# Pg7-Power_supply_2.net
KiCad netlist of a schematic drawn in Altium Designer
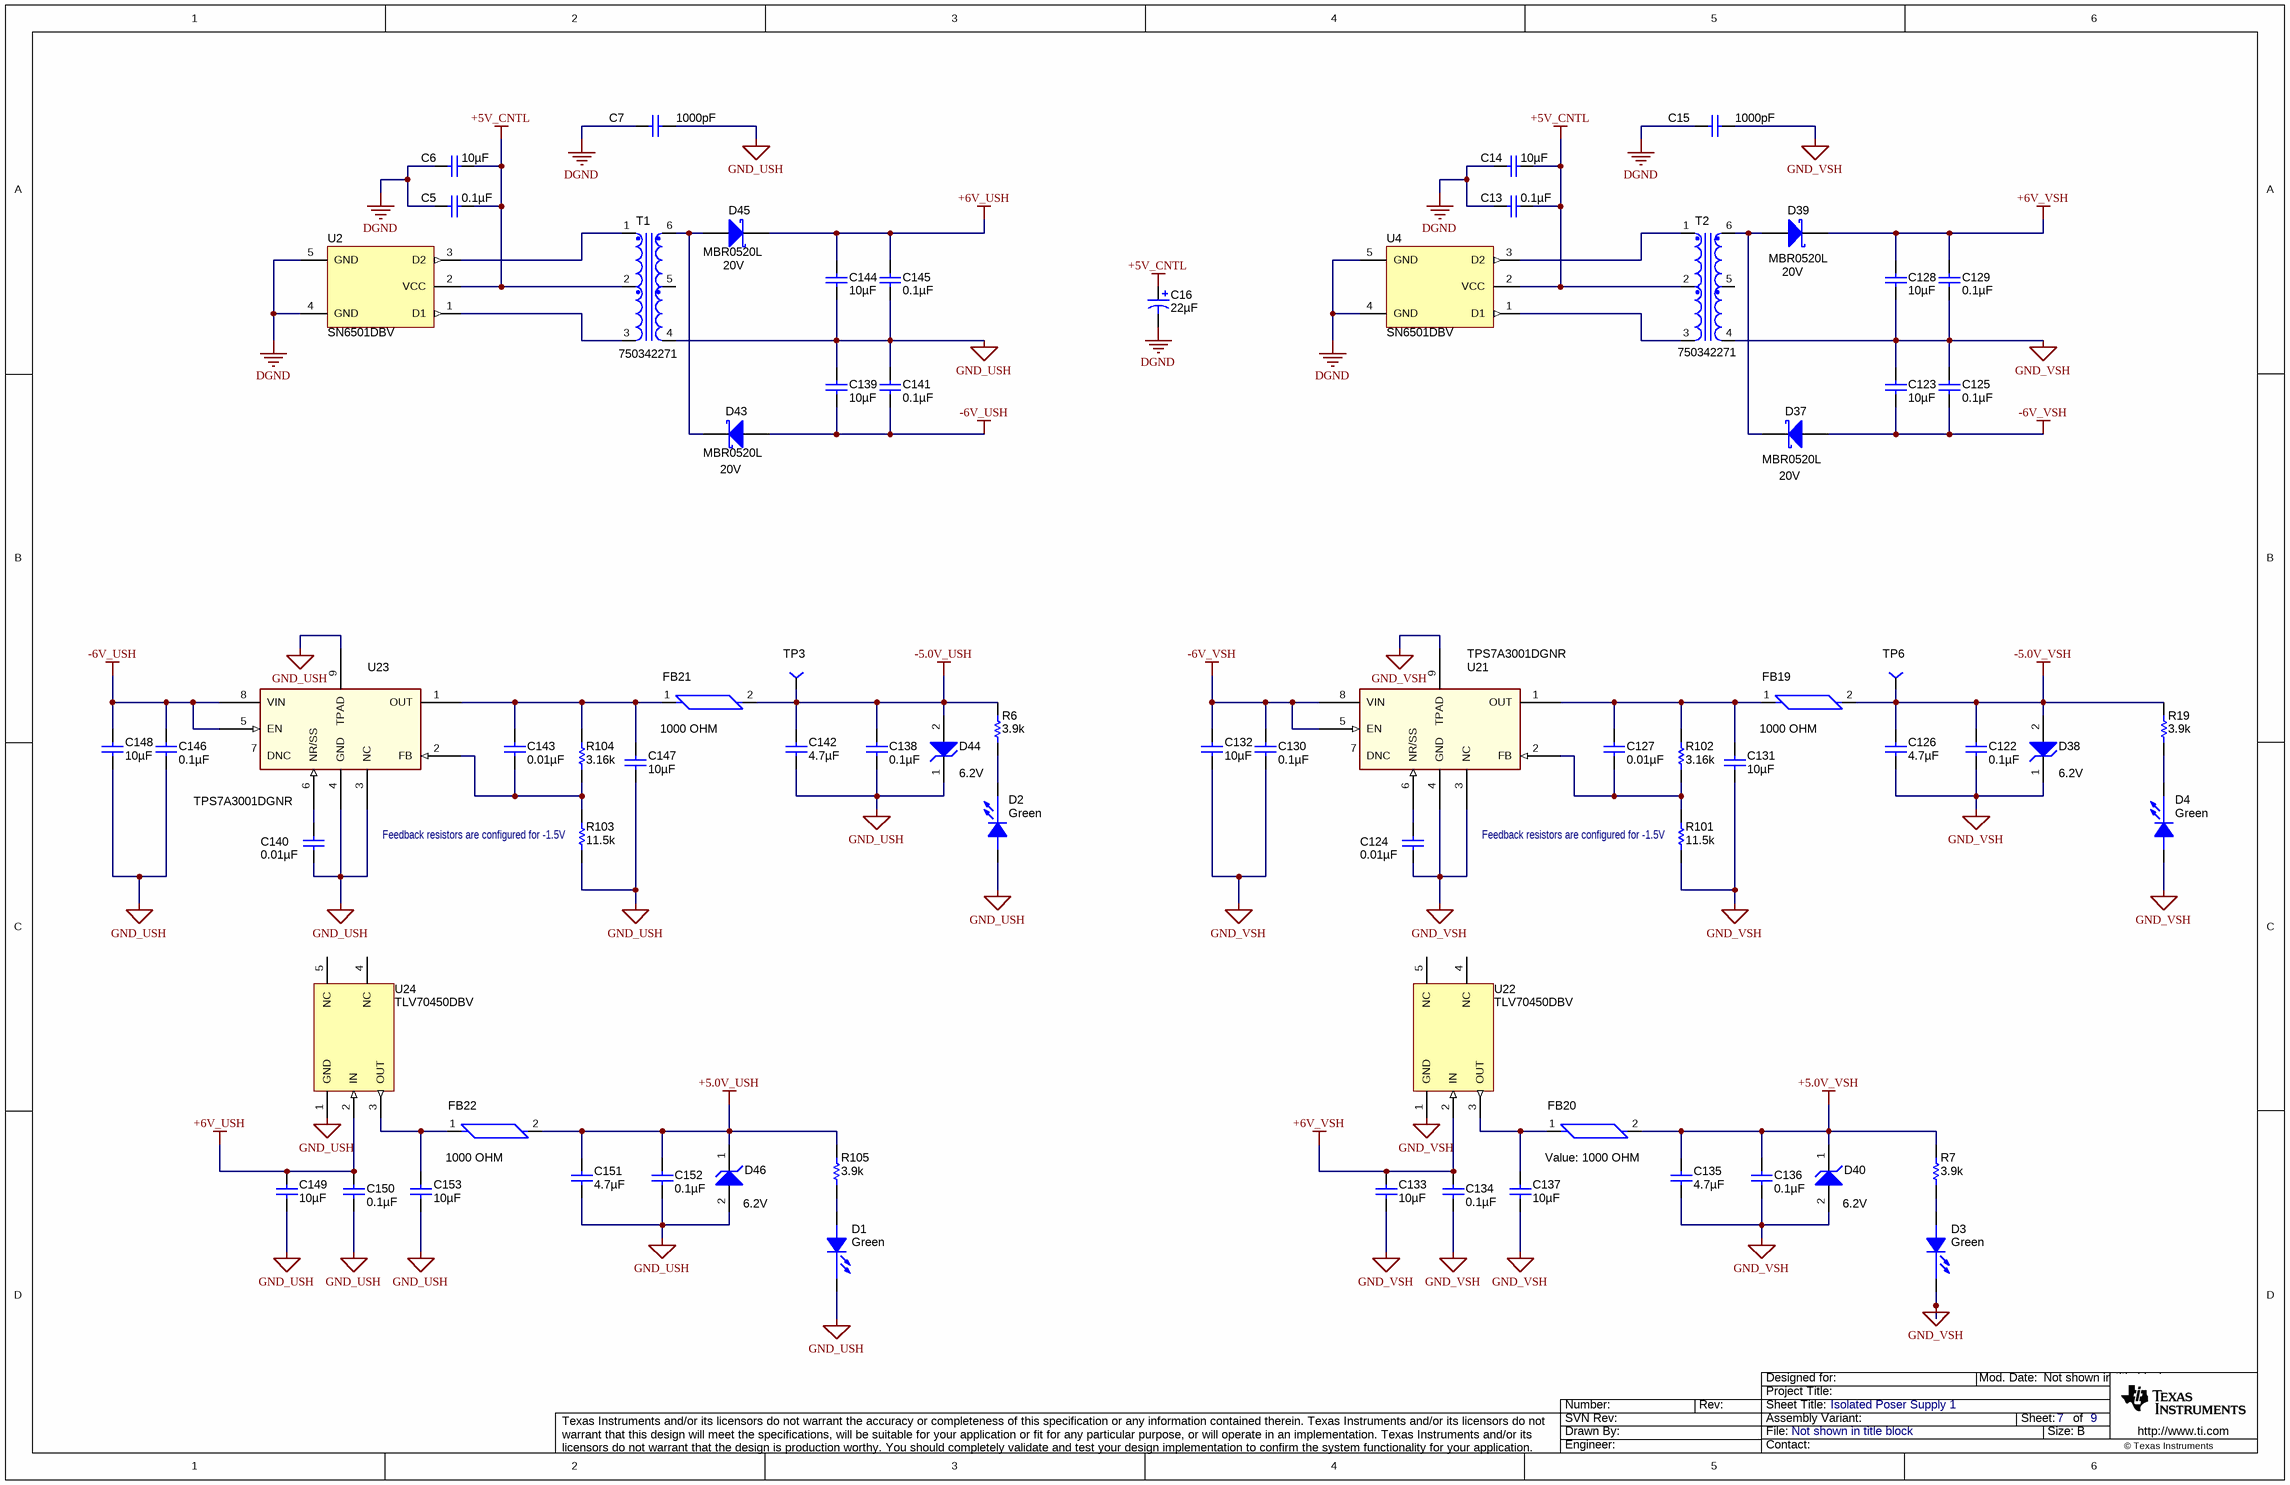
[diagram p0: Pg7-Power supply 2.SchDoc]

(export (version "E")
  (design (tool "Eeschema 10.0.6"))
  (components
    (comp (ref "C5")
      (value "~")
      (footprint "0603")
      (description "CAP, CERM, 0.1uF, 50V, +/-10%, X7R, 0603")
      (fields
        (field (name "PARTNUMBER") "C0603C104K5RACTU")
        (field (name "VALUEDISPLAYED") "0.1µF")
        (field (name "MANUFACTURER") "Kemet")
        (field (name "PUBLISHER") "Texas Instruments")
      )
      (libsource (lib "Capacitor_Ceramic") (part "C0603C104K5RACTU"))
    )
    (comp (ref "C6")
      (value "~")
      (footprint "1210")
      (description "CAP, CERM, 10uF, 35V, +/-20%, X7R, 1210")
      (fields
        (field (name "PARTNUMBER") "GMK325AB7106MM-T")
        (field (name "VALUEDISPLAYED") "10µF")
        (field (name "MANUFACTURER") "Taiyo Yuden")
        (field (name "PUBLISHER") "Texas Instruments")
      )
      (libsource (lib "Capacitor_Ceramic") (part "GMK325AB7106MM-T"))
    )
    (comp (ref "C7")
      (value "1000pF")
      (footprint "CAP_200mil")
      (description "CAP CER 1000PF 1KV 10% RADIAL")
      (fields
        (field (name "PARTNUMBER") "S102K29Y5PN63J5R")
        (field (name "MANUFACTURER") "Vishay BC Components")
        (field (name "PUBLISHER") "Texas Instruments")
      )
      (libsource (lib "TI-INDIA-ALTIUM") (part "202R18W102KV4E"))
    )
    (comp (ref "C13")
      (value "~")
      (footprint "0603")
      (description "CAP, CERM, 0.1uF, 50V, +/-10%, X7R, 0603")
      (fields
        (field (name "PARTNUMBER") "C0603C104K5RACTU")
        (field (name "VALUEDISPLAYED") "0.1µF")
        (field (name "MANUFACTURER") "Kemet")
        (field (name "PUBLISHER") "Texas Instruments")
      )
      (libsource (lib "Capacitor_Ceramic") (part "C0603C104K5RACTU"))
    )
    (comp (ref "C14")
      (value "~")
      (footprint "1210")
      (description "CAP, CERM, 10uF, 35V, +/-20%, X7R, 1210")
      (fields
        (field (name "PARTNUMBER") "GMK325AB7106MM-T")
        (field (name "VALUEDISPLAYED") "10µF")
        (field (name "MANUFACTURER") "Taiyo Yuden")
        (field (name "PUBLISHER") "Texas Instruments")
      )
      (libsource (lib "Capacitor_Ceramic") (part "GMK325AB7106MM-T"))
    )
    (comp (ref "C15")
      (value "1000pF")
      (footprint "CAP_200mil")
      (description "CAP CER 1000PF 1KV 10% RADIAL")
      (fields
        (field (name "PARTNUMBER") "S102K29Y5PN63J5R")
        (field (name "MANUFACTURER") "Vishay BC Components")
        (field (name "PUBLISHER") "Texas Instruments")
      )
      (libsource (lib "TI-INDIA-ALTIUM") (part "202R18W102KV4E"))
    )
    (comp (ref "C16")
      (value "UUD1E220MCL1GS")
      (footprint "SM_RADIAL_5MM")
      (description "CAP, AL, 22uF, 25V, +/-20%, 0.76 ohm, SMD")
      (fields
        (field (name "VALUEDISPLAYED") "22µF")
        (field (name "MANUFACTURER") "Nichicon")
        (field (name "PUBLISHER") "Texas Instruments")
      )
      (libsource (lib "Capacitor_Aluminum") (part "UUD1E220MCL1GS"))
    )
    (comp (ref "C122")
      (value "~")
      (footprint "0603")
      (description "CAP, CERM, 0.1uF, 50V, +/-10%, X7R, 0603")
      (fields
        (field (name "PARTNUMBER") "C0603C104K5RACTU")
        (field (name "VALUEDISPLAYED") "0.1µF")
        (field (name "MANUFACTURER") "Kemet")
        (field (name "PUBLISHER") "Texas Instruments")
      )
      (libsource (lib "Capacitor_Ceramic") (part "C0603C104K5RACTU"))
    )
    (comp (ref "C123")
      (value "~")
      (footprint "1210")
      (description "CAP, CERM, 10uF, 35V, +/-20%, X7R, 1210")
      (fields
        (field (name "PARTNUMBER") "GMK325AB7106MM-T")
        (field (name "VALUEDISPLAYED") "10µF")
        (field (name "MANUFACTURER") "Taiyo Yuden")
        (field (name "PUBLISHER") "Texas Instruments")
      )
      (libsource (lib "Capacitor_Ceramic") (part "GMK325AB7106MM-T"))
    )
    (comp (ref "C124")
      (value "~")
      (footprint "0603")
      (description "CAP, CERM, 0.01uF, 100V, +/-5%, X7R, 0603")
      (fields
        (field (name "PARTNUMBER") "06031C103J4Z4A")
        (field (name "VALUEDISPLAYED") "0.01µF")
        (field (name "MANUFACTURER") "AVX")
        (field (name "PUBLISHER") "Texas Instruments")
      )
      (libsource (lib "Capacitor_Ceramic") (part "06031C103JAT2A"))
    )
    (comp (ref "C125")
      (value "~")
      (footprint "0603")
      (description "CAP, CERM, 0.1uF, 50V, +/-10%, X7R, 0603")
      (fields
        (field (name "PARTNUMBER") "C0603C104K5RACTU")
        (field (name "VALUEDISPLAYED") "0.1µF")
        (field (name "MANUFACTURER") "Kemet")
        (field (name "PUBLISHER") "Texas Instruments")
      )
      (libsource (lib "Capacitor_Ceramic") (part "C0603C104K5RACTU"))
    )
    (comp (ref "C126")
      (value "~")
      (footprint "0805_HV")
      (description "CAP, CERM, 4.7uF, 50V, +/-10%, X5R, 0805")
      (fields
        (field (name "PARTNUMBER") "C2012X5R1H475K125AB")
        (field (name "VALUEDISPLAYED") "4.7µF")
        (field (name "MANUFACTURER") "TDK")
        (field (name "PUBLISHER") "Texas Instruments")
      )
      (libsource (lib "Capacitor_Ceramic") (part "C2012X5R1H475K125AB"))
    )
    (comp (ref "C127")
      (value "~")
      (footprint "0603")
      (description "CAP, CERM, 0.01uF, 100V, +/-5%, X7R, 0603")
      (fields
        (field (name "PARTNUMBER") "06031C103J4Z4A")
        (field (name "VALUEDISPLAYED") "0.01µF")
        (field (name "MANUFACTURER") "AVX")
        (field (name "PUBLISHER") "Texas Instruments")
      )
      (libsource (lib "Capacitor_Ceramic") (part "06031C103JAT2A"))
    )
    (comp (ref "C128")
      (value "~")
      (footprint "1210")
      (description "CAP, CERM, 10uF, 35V, +/-20%, X7R, 1210")
      (fields
        (field (name "PARTNUMBER") "GMK325AB7106MM-T")
        (field (name "VALUEDISPLAYED") "10µF")
        (field (name "MANUFACTURER") "Taiyo Yuden")
        (field (name "PUBLISHER") "Texas Instruments")
      )
      (libsource (lib "Capacitor_Ceramic") (part "GMK325AB7106MM-T"))
    )
    (comp (ref "C129")
      (value "~")
      (footprint "0603")
      (description "CAP, CERM, 0.1uF, 50V, +/-10%, X7R, 0603")
      (fields
        (field (name "PARTNUMBER") "C0603C104K5RACTU")
        (field (name "VALUEDISPLAYED") "0.1µF")
        (field (name "MANUFACTURER") "Kemet")
        (field (name "PUBLISHER") "Texas Instruments")
      )
      (libsource (lib "Capacitor_Ceramic") (part "C0603C104K5RACTU"))
    )
    (comp (ref "C130")
      (value "~")
      (footprint "0603")
      (description "CAP, CERM, 0.1uF, 50V, +/-10%, X7R, 0603")
      (fields
        (field (name "PARTNUMBER") "C0603C104K5RACTU")
        (field (name "VALUEDISPLAYED") "0.1µF")
        (field (name "MANUFACTURER") "Kemet")
        (field (name "PUBLISHER") "Texas Instruments")
      )
      (libsource (lib "Capacitor_Ceramic") (part "C0603C104K5RACTU"))
    )
    (comp (ref "C131")
      (value "~")
      (footprint "1210")
      (description "CAP, CERM, 10uF, 35V, +/-20%, X7R, 1210")
      (fields
        (field (name "PARTNUMBER") "GMK325AB7106MM-T")
        (field (name "VALUEDISPLAYED") "10µF")
        (field (name "MANUFACTURER") "Taiyo Yuden")
        (field (name "PUBLISHER") "Texas Instruments")
      )
      (libsource (lib "Capacitor_Ceramic") (part "GMK325AB7106MM-T"))
    )
    (comp (ref "C132")
      (value "~")
      (footprint "1210")
      (description "CAP, CERM, 10uF, 35V, +/-20%, X7R, 1210")
      (fields
        (field (name "PARTNUMBER") "GMK325AB7106MM-T")
        (field (name "VALUEDISPLAYED") "10µF")
        (field (name "MANUFACTURER") "Taiyo Yuden")
        (field (name "PUBLISHER") "Texas Instruments")
      )
      (libsource (lib "Capacitor_Ceramic") (part "GMK325AB7106MM-T"))
    )
    (comp (ref "C133")
      (value "~")
      (footprint "1210")
      (description "CAP, CERM, 10uF, 35V, +/-20%, X7R, 1210")
      (fields
        (field (name "PARTNUMBER") "GMK325AB7106MM-T")
        (field (name "VALUEDISPLAYED") "10µF")
        (field (name "MANUFACTURER") "Taiyo Yuden")
        (field (name "PUBLISHER") "Texas Instruments")
      )
      (libsource (lib "Capacitor_Ceramic") (part "GMK325AB7106MM-T"))
    )
    (comp (ref "C134")
      (value "~")
      (footprint "0603")
      (description "CAP, CERM, 0.1uF, 50V, +/-10%, X7R, 0603")
      (fields
        (field (name "PARTNUMBER") "C0603C104K5RACTU")
        (field (name "VALUEDISPLAYED") "0.1µF")
        (field (name "MANUFACTURER") "Kemet")
        (field (name "PUBLISHER") "Texas Instruments")
      )
      (libsource (lib "Capacitor_Ceramic") (part "C0603C104K5RACTU"))
    )
    (comp (ref "C135")
      (value "~")
      (footprint "0805_HV")
      (description "CAP, CERM, 4.7uF, 50V, +/-10%, X5R, 0805")
      (fields
        (field (name "PARTNUMBER") "C2012X5R1H475K125AB")
        (field (name "VALUEDISPLAYED") "4.7µF")
        (field (name "MANUFACTURER") "TDK")
        (field (name "PUBLISHER") "Texas Instruments")
      )
      (libsource (lib "Capacitor_Ceramic") (part "C2012X5R1H475K125AB"))
    )
    (comp (ref "C136")
      (value "~")
      (footprint "0603")
      (description "CAP, CERM, 0.1uF, 50V, +/-10%, X7R, 0603")
      (fields
        (field (name "PARTNUMBER") "C0603C104K5RACTU")
        (field (name "VALUEDISPLAYED") "0.1µF")
        (field (name "MANUFACTURER") "Kemet")
        (field (name "PUBLISHER") "Texas Instruments")
      )
      (libsource (lib "Capacitor_Ceramic") (part "C0603C104K5RACTU"))
    )
    (comp (ref "C137")
      (value "~")
      (footprint "1210")
      (description "CAP, CERM, 10uF, 35V, +/-20%, X7R, 1210")
      (fields
        (field (name "PARTNUMBER") "GMK325AB7106MM-T")
        (field (name "VALUEDISPLAYED") "10µF")
        (field (name "MANUFACTURER") "Taiyo Yuden")
        (field (name "PUBLISHER") "Texas Instruments")
      )
      (libsource (lib "Capacitor_Ceramic") (part "GMK325AB7106MM-T"))
    )
    (comp (ref "C138")
      (value "~")
      (footprint "0603")
      (description "CAP, CERM, 0.1uF, 50V, +/-10%, X7R, 0603")
      (fields
        (field (name "PARTNUMBER") "C0603C104K5RACTU")
        (field (name "VALUEDISPLAYED") "0.1µF")
        (field (name "MANUFACTURER") "Kemet")
        (field (name "PUBLISHER") "Texas Instruments")
      )
      (libsource (lib "Capacitor_Ceramic") (part "C0603C104K5RACTU"))
    )
    (comp (ref "C139")
      (value "~")
      (footprint "1210")
      (description "CAP, CERM, 10uF, 35V, +/-20%, X7R, 1210")
      (fields
        (field (name "PARTNUMBER") "GMK325AB7106MM-T")
        (field (name "VALUEDISPLAYED") "10µF")
        (field (name "MANUFACTURER") "Taiyo Yuden")
        (field (name "PUBLISHER") "Texas Instruments")
      )
      (libsource (lib "Capacitor_Ceramic") (part "GMK325AB7106MM-T"))
    )
    (comp (ref "C140")
      (value "~")
      (footprint "0603")
      (description "CAP, CERM, 0.01uF, 100V, +/-5%, X7R, 0603")
      (fields
        (field (name "PARTNUMBER") "06031C103J4Z4A")
        (field (name "VALUEDISPLAYED") "0.01µF")
        (field (name "MANUFACTURER") "AVX")
        (field (name "PUBLISHER") "Texas Instruments")
      )
      (libsource (lib "Capacitor_Ceramic") (part "06031C103JAT2A"))
    )
    (comp (ref "C141")
      (value "~")
      (footprint "0603")
      (description "CAP, CERM, 0.1uF, 50V, +/-10%, X7R, 0603")
      (fields
        (field (name "PARTNUMBER") "C0603C104K5RACTU")
        (field (name "VALUEDISPLAYED") "0.1µF")
        (field (name "MANUFACTURER") "Kemet")
        (field (name "PUBLISHER") "Texas Instruments")
      )
      (libsource (lib "Capacitor_Ceramic") (part "C0603C104K5RACTU"))
    )
    (comp (ref "C142")
      (value "~")
      (footprint "0805_HV")
      (description "CAP, CERM, 4.7uF, 50V, +/-10%, X5R, 0805")
      (fields
        (field (name "PARTNUMBER") "C2012X5R1H475K125AB")
        (field (name "VALUEDISPLAYED") "4.7µF")
        (field (name "MANUFACTURER") "TDK")
        (field (name "PUBLISHER") "Texas Instruments")
      )
      (libsource (lib "Capacitor_Ceramic") (part "C2012X5R1H475K125AB"))
    )
    (comp (ref "C143")
      (value "~")
      (footprint "0603")
      (description "CAP, CERM, 0.01uF, 100V, +/-5%, X7R, 0603")
      (fields
        (field (name "PARTNUMBER") "06031C103J4Z4A")
        (field (name "VALUEDISPLAYED") "0.01µF")
        (field (name "MANUFACTURER") "AVX")
        (field (name "PUBLISHER") "Texas Instruments")
      )
      (libsource (lib "Capacitor_Ceramic") (part "06031C103JAT2A"))
    )
    (comp (ref "C144")
      (value "~")
      (footprint "1210")
      (description "CAP, CERM, 10uF, 35V, +/-20%, X7R, 1210")
      (fields
        (field (name "PARTNUMBER") "GMK325AB7106MM-T")
        (field (name "VALUEDISPLAYED") "10µF")
        (field (name "MANUFACTURER") "Taiyo Yuden")
        (field (name "PUBLISHER") "Texas Instruments")
      )
      (libsource (lib "Capacitor_Ceramic") (part "GMK325AB7106MM-T"))
    )
    (comp (ref "C145")
      (value "~")
      (footprint "0603")
      (description "CAP, CERM, 0.1uF, 50V, +/-10%, X7R, 0603")
      (fields
        (field (name "PARTNUMBER") "C0603C104K5RACTU")
        (field (name "VALUEDISPLAYED") "0.1µF")
        (field (name "MANUFACTURER") "Kemet")
        (field (name "PUBLISHER") "Texas Instruments")
      )
      (libsource (lib "Capacitor_Ceramic") (part "C0603C104K5RACTU"))
    )
    (comp (ref "C146")
      (value "~")
      (footprint "0603")
      (description "CAP, CERM, 0.1uF, 50V, +/-10%, X7R, 0603")
      (fields
        (field (name "PARTNUMBER") "C0603C104K5RACTU")
        (field (name "VALUEDISPLAYED") "0.1µF")
        (field (name "MANUFACTURER") "Kemet")
        (field (name "PUBLISHER") "Texas Instruments")
      )
      (libsource (lib "Capacitor_Ceramic") (part "C0603C104K5RACTU"))
    )
    (comp (ref "C147")
      (value "~")
      (footprint "1210")
      (description "CAP, CERM, 10uF, 35V, +/-20%, X7R, 1210")
      (fields
        (field (name "PARTNUMBER") "GMK325AB7106MM-T")
        (field (name "VALUEDISPLAYED") "10µF")
        (field (name "MANUFACTURER") "Taiyo Yuden")
        (field (name "PUBLISHER") "Texas Instruments")
      )
      (libsource (lib "Capacitor_Ceramic") (part "GMK325AB7106MM-T"))
    )
    (comp (ref "C148")
      (value "~")
      (footprint "1210")
      (description "CAP, CERM, 10uF, 35V, +/-20%, X7R, 1210")
      (fields
        (field (name "PARTNUMBER") "GMK325AB7106MM-T")
        (field (name "VALUEDISPLAYED") "10µF")
        (field (name "MANUFACTURER") "Taiyo Yuden")
        (field (name "PUBLISHER") "Texas Instruments")
      )
      (libsource (lib "Capacitor_Ceramic") (part "GMK325AB7106MM-T"))
    )
    (comp (ref "C149")
      (value "~")
      (footprint "1210")
      (description "CAP, CERM, 10uF, 35V, +/-20%, X7R, 1210")
      (fields
        (field (name "PARTNUMBER") "GMK325AB7106MM-T")
        (field (name "VALUEDISPLAYED") "10µF")
        (field (name "MANUFACTURER") "Taiyo Yuden")
        (field (name "PUBLISHER") "Texas Instruments")
      )
      (libsource (lib "Capacitor_Ceramic") (part "GMK325AB7106MM-T"))
    )
    (comp (ref "C150")
      (value "~")
      (footprint "0603")
      (description "CAP, CERM, 0.1uF, 50V, +/-10%, X7R, 0603")
      (fields
        (field (name "PARTNUMBER") "C0603C104K5RACTU")
        (field (name "VALUEDISPLAYED") "0.1µF")
        (field (name "MANUFACTURER") "Kemet")
        (field (name "PUBLISHER") "Texas Instruments")
      )
      (libsource (lib "Capacitor_Ceramic") (part "C0603C104K5RACTU"))
    )
    (comp (ref "C151")
      (value "~")
      (footprint "0805_HV")
      (description "CAP, CERM, 4.7uF, 50V, +/-10%, X5R, 0805")
      (fields
        (field (name "PARTNUMBER") "C2012X5R1H475K125AB")
        (field (name "VALUEDISPLAYED") "4.7µF")
        (field (name "MANUFACTURER") "TDK")
        (field (name "PUBLISHER") "Texas Instruments")
      )
      (libsource (lib "Capacitor_Ceramic") (part "C2012X5R1H475K125AB"))
    )
    (comp (ref "C152")
      (value "~")
      (footprint "0603")
      (description "CAP, CERM, 0.1uF, 50V, +/-10%, X7R, 0603")
      (fields
        (field (name "PARTNUMBER") "C0603C104K5RACTU")
        (field (name "VALUEDISPLAYED") "0.1µF")
        (field (name "MANUFACTURER") "Kemet")
        (field (name "PUBLISHER") "Texas Instruments")
      )
      (libsource (lib "Capacitor_Ceramic") (part "C0603C104K5RACTU"))
    )
    (comp (ref "C153")
      (value "~")
      (footprint "1210")
      (description "CAP, CERM, 10uF, 35V, +/-20%, X7R, 1210")
      (fields
        (field (name "PARTNUMBER") "GMK325AB7106MM-T")
        (field (name "VALUEDISPLAYED") "10µF")
        (field (name "MANUFACTURER") "Taiyo Yuden")
        (field (name "PUBLISHER") "Texas Instruments")
      )
      (libsource (lib "Capacitor_Ceramic") (part "GMK325AB7106MM-T"))
    )
    (comp (ref "D1")
      (value "Green")
      (footprint "LED0603AA")
      (description "LED SmartLED Green 570NM")
      (fields
        (field (name "PARTNUMBER") "LG L29K-G2J1-24-Z")
        (field (name "MANUFACTURER") "OSRAM")
        (field (name "PUBLISHER") "TI")
        (field (name "SYMBOLCREATOR") "x0120606")
      )
      (libsource (lib "TI-INDIA-ALTIUM") (part "LED_LG L29K-G2J1-24-Z"))
    )
    (comp (ref "D2")
      (value "Green")
      (footprint "LED0603AA")
      (description "LED SmartLED Green 570NM")
      (fields
        (field (name "PARTNUMBER") "LG L29K-G2J1-24-Z")
        (field (name "MANUFACTURER") "OSRAM")
        (field (name "PUBLISHER") "TI")
        (field (name "SYMBOLCREATOR") "x0120606")
      )
      (libsource (lib "TI-INDIA-ALTIUM") (part "LED_LG L29K-G2J1-24-Z"))
    )
    (comp (ref "D3")
      (value "Green")
      (footprint "LED0603AA")
      (description "LED SmartLED Green 570NM")
      (fields
        (field (name "PARTNUMBER") "LG L29K-G2J1-24-Z")
        (field (name "MANUFACTURER") "OSRAM")
        (field (name "PUBLISHER") "TI")
        (field (name "SYMBOLCREATOR") "x0120606")
      )
      (libsource (lib "TI-INDIA-ALTIUM") (part "LED_LG L29K-G2J1-24-Z"))
    )
    (comp (ref "D4")
      (value "Green")
      (footprint "LED0603AA")
      (description "LED SmartLED Green 570NM")
      (fields
        (field (name "PARTNUMBER") "LG L29K-G2J1-24-Z")
        (field (name "MANUFACTURER") "OSRAM")
        (field (name "PUBLISHER") "TI")
        (field (name "SYMBOLCREATOR") "x0120606")
      )
      (libsource (lib "TI-INDIA-ALTIUM") (part "LED_LG L29K-G2J1-24-Z"))
    )
    (comp (ref "D37")
      (value "MBR0520L")
      (footprint "SOD-123")
      (description "Diode, Schottky, 20V, 0.5A, SOD-123")
      (fields
        (field (name "ALTIUM_VALUE") "20V")
        (field (name "MANUFACTURER") "Fairchild Semiconductor")
        (field (name "PUBLISHER") "Texas Instruments")
      )
      (libsource (lib "Diode") (part "MBR0520LT1G"))
    )
    (comp (ref "D38")
      (value "6.2V")
      (footprint "powerDI123")
      (description "Diode, Zener, 6.2V, 1W, PowerDI123")
      (fields
        (field (name "PARTNUMBER") "DFLZ6V2-7")
        (field (name "MANUFACTURER") "Diodes Inc.")
        (field (name "PUBLISHER") "Texas Instruments")
      )
      (libsource (lib "ZenerDiodes") (part "DFLZ6V2-7"))
    )
    (comp (ref "D39")
      (value "MBR0520L")
      (footprint "SOD-123")
      (description "Diode, Schottky, 20V, 0.5A, SOD-123")
      (fields
        (field (name "ALTIUM_VALUE") "20V")
        (field (name "MANUFACTURER") "Fairchild Semiconductor")
        (field (name "PUBLISHER") "Texas Instruments")
      )
      (libsource (lib "Diode") (part "MBR0520LT1G"))
    )
    (comp (ref "D40")
      (value "6.2V")
      (footprint "powerDI123")
      (description "Diode, Zener, 6.2V, 1W, PowerDI123")
      (fields
        (field (name "PARTNUMBER") "DFLZ6V2-7")
        (field (name "MANUFACTURER") "Diodes Inc.")
        (field (name "PUBLISHER") "Texas Instruments")
      )
      (libsource (lib "ZenerDiodes") (part "DFLZ6V2-7"))
    )
    (comp (ref "D43")
      (value "MBR0520L")
      (footprint "SOD-123")
      (description "Diode, Schottky, 20V, 0.5A, SOD-123")
      (fields
        (field (name "ALTIUM_VALUE") "20V")
        (field (name "MANUFACTURER") "Fairchild Semiconductor")
        (field (name "PUBLISHER") "Texas Instruments")
      )
      (libsource (lib "Diode") (part "MBR0520LT1G"))
    )
    (comp (ref "D44")
      (value "6.2V")
      (footprint "powerDI123")
      (description "Diode, Zener, 6.2V, 1W, PowerDI123")
      (fields
        (field (name "PARTNUMBER") "DFLZ6V2-7")
        (field (name "MANUFACTURER") "Diodes Inc.")
        (field (name "PUBLISHER") "Texas Instruments")
      )
      (libsource (lib "ZenerDiodes") (part "DFLZ6V2-7"))
    )
    (comp (ref "D45")
      (value "MBR0520L")
      (footprint "SOD-123")
      (description "Diode, Schottky, 20V, 0.5A, SOD-123")
      (fields
        (field (name "ALTIUM_VALUE") "20V")
        (field (name "MANUFACTURER") "Fairchild Semiconductor")
        (field (name "PUBLISHER") "Texas Instruments")
      )
      (libsource (lib "Diode") (part "MBR0520LT1G"))
    )
    (comp (ref "D46")
      (value "6.2V")
      (footprint "powerDI123")
      (description "Diode, Zener, 6.2V, 1W, PowerDI123")
      (fields
        (field (name "PARTNUMBER") "DFLZ6V2-7")
        (field (name "MANUFACTURER") "Diodes Inc.")
        (field (name "PUBLISHER") "Texas Instruments")
      )
      (libsource (lib "ZenerDiodes") (part "DFLZ6V2-7"))
    )
    (comp (ref "FB19")
      (value "1000 OHM")
      (footprint "FB0603")
      (description "FERRITE CHIP 1000 OHM 300MA 0603")
      (fields
        (field (name "PARTNUMBER") "MMZ1608B102C")
        (field (name "MANUFACTURER") "TDK Corporation")
        (field (name "PUBLISHER") "TI")
      )
      (libsource (lib "TI-INDIA-ALTIUM") (part "MMZ1608B102C"))
    )
    (comp (ref "FB20")
      (value "1000 OHM")
      (footprint "FB0603")
      (description "FERRITE CHIP 1000 OHM 300MA 0603")
      (fields
        (field (name "PARTNUMBER") "MMZ1608B102C")
        (field (name "MANUFACTURER") "TDK Corporation")
        (field (name "PUBLISHER") "TI")
      )
      (libsource (lib "TI-INDIA-ALTIUM") (part "MMZ1608B102C"))
    )
    (comp (ref "FB21")
      (value "1000 OHM")
      (footprint "FB0603")
      (description "FERRITE CHIP 1000 OHM 300MA 0603")
      (fields
        (field (name "PARTNUMBER") "MMZ1608B102C")
        (field (name "MANUFACTURER") "TDK Corporation")
        (field (name "PUBLISHER") "TI")
      )
      (libsource (lib "TI-INDIA-ALTIUM") (part "MMZ1608B102C"))
    )
    (comp (ref "FB22")
      (value "1000 OHM")
      (footprint "FB0603")
      (description "FERRITE CHIP 1000 OHM 300MA 0603")
      (fields
        (field (name "PARTNUMBER") "MMZ1608B102C")
        (field (name "MANUFACTURER") "TDK Corporation")
        (field (name "PUBLISHER") "TI")
      )
      (libsource (lib "TI-INDIA-ALTIUM") (part "MMZ1608B102C"))
    )
    (comp (ref "R6")
      (value "3.9k")
      (footprint "0603")
      (description "RES, 3.9k ohm, 5%, 0.1W, 0603")
      (fields
        (field (name "PARTNUMBER") "CRCW06033K90JNEA")
        (field (name "MANUFACTURER") "Vishay-Dale")
        (field (name "PUBLISHER") "Texas Instruments")
      )
      (libsource (lib "Resistor_0603") (part "CRCW06033K90JNEA"))
    )
    (comp (ref "R7")
      (value "3.9k")
      (footprint "0603")
      (description "RES, 3.9k ohm, 5%, 0.1W, 0603")
      (fields
        (field (name "PARTNUMBER") "CRCW06033K90JNEA")
        (field (name "MANUFACTURER") "Vishay-Dale")
        (field (name "PUBLISHER") "Texas Instruments")
      )
      (libsource (lib "Resistor_0603") (part "CRCW06033K90JNEA"))
    )
    (comp (ref "R19")
      (value "3.9k")
      (footprint "0603")
      (description "RES, 3.9k ohm, 5%, 0.1W, 0603")
      (fields
        (field (name "PARTNUMBER") "CRCW06033K90JNEA")
        (field (name "MANUFACTURER") "Vishay-Dale")
        (field (name "PUBLISHER") "Texas Instruments")
      )
      (libsource (lib "Resistor_0603") (part "CRCW06033K90JNEA"))
    )
    (comp (ref "R101")
      (value "11.5k")
      (footprint "0603")
      (description "RES, 11.5k ohm, 1%, 0.1W, 0603")
      (fields
        (field (name "PARTNUMBER") "CRCW060311K5FKEA")
        (field (name "MANUFACTURER") "Vishay-Dale")
        (field (name "PUBLISHER") "Texas Instruments")
      )
      (libsource (lib "Resistor_0603") (part "CRCW060311K5FKEA"))
    )
    (comp (ref "R102")
      (value "RC0603FR-073K16L")
      (footprint "0603")
      (description "RES, 3.16 k, 1%, 0.1 W, 0603")
      (fields
        (field (name "VALUEDISPLAYED") "3.16k")
        (field (name "MANUFACTURER") "Yageo America")
        (field (name "PUBLISHER") "Texas Instruments")
      )
      (libsource (lib "Resistor_0603") (part "RC0603FR-073K16L"))
    )
    (comp (ref "R103")
      (value "11.5k")
      (footprint "0603")
      (description "RES, 11.5k ohm, 1%, 0.1W, 0603")
      (fields
        (field (name "PARTNUMBER") "CRCW060311K5FKEA")
        (field (name "MANUFACTURER") "Vishay-Dale")
        (field (name "PUBLISHER") "Texas Instruments")
      )
      (libsource (lib "Resistor_0603") (part "CRCW060311K5FKEA"))
    )
    (comp (ref "R104")
      (value "RC0603FR-073K16L")
      (footprint "0603")
      (description "RES, 3.16 k, 1%, 0.1 W, 0603")
      (fields
        (field (name "VALUEDISPLAYED") "3.16k")
        (field (name "MANUFACTURER") "Yageo America")
        (field (name "PUBLISHER") "Texas Instruments")
      )
      (libsource (lib "Resistor_0603") (part "RC0603FR-073K16L"))
    )
    (comp (ref "R105")
      (value "3.9k")
      (footprint "0603")
      (description "RES, 3.9k ohm, 5%, 0.1W, 0603")
      (fields
        (field (name "PARTNUMBER") "CRCW06033K90JNEA")
        (field (name "MANUFACTURER") "Vishay-Dale")
        (field (name "PUBLISHER") "Texas Instruments")
      )
      (libsource (lib "Resistor_0603") (part "CRCW06033K90JNEA"))
    )
    (comp (ref "T1")
      (value "750342271")
      (footprint "760390015")
      (description "Transformer 469uH SMD")
      (fields (field (name "MANUFACTURER") "Wurth Electronics Midcom") (field (name "PUBLISHER") "TI"))
      (libsource (lib "Isolated current sensing") (part "TRNSFMR"))
    )
    (comp (ref "T2")
      (value "750342271")
      (footprint "760390015")
      (description "Transformer 469uH SMD")
      (fields (field (name "MANUFACTURER") "Wurth Electronics Midcom") (field (name "PUBLISHER") "TI"))
      (libsource (lib "Isolated current sensing") (part "TRNSFMR"))
    )
    (comp (ref "TP3")
      (value "~")
      (footprint "TP-040_RND")
      (description "Test Point, O.040 Hole")
      (fields (field (name "MANUFACTURER") "STD"))
      (libsource (lib "PADSlegacy_Hardware") (part "TP-040_RND"))
    )
    (comp (ref "TP6")
      (value "~")
      (footprint "TP-040_RND")
      (description "Test Point, O.040 Hole")
      (fields (field (name "MANUFACTURER") "STD"))
      (libsource (lib "PADSlegacy_Hardware") (part "TP-040_RND"))
    )
    (comp (ref "U2")
      (value "SN6501DBV")
      (footprint "DBV0005A_N")
      (description "Transformer Driver for Isolated Power Supplies, DBV0005A")
      (fields
        (field (name "MANUFACTURER") "Texas Instruments")
        (field (name "SYMBOLCREATOR") "a0411947")
        (field (name "PUBLISHER") "Texas Instruments")
      )
      (libsource (lib "TI_Pre_Release") (part "SN6501DBV"))
    )
    (comp (ref "U4")
      (value "SN6501DBV")
      (footprint "DBV0005A_N")
      (description "Transformer Driver for Isolated Power Supplies, DBV0005A")
      (fields
        (field (name "MANUFACTURER") "Texas Instruments")
        (field (name "SYMBOLCREATOR") "a0411947")
        (field (name "PUBLISHER") "Texas Instruments")
      )
      (libsource (lib "TI_Pre_Release") (part "SN6501DBV"))
    )
    (comp (ref "U21")
      (value "~")
      (footprint "MSOP8(DGN)")
      (description "-36V, -200mA, Ultralow-Noise, Negative Linear Regulator")
      (fields
        (field (name "MANUFACTURER") "Texas Instruments")
        (field (name "PARTNUMBER") "TPS7A3001DGNR")
        (field (name "PUBLISHER") "Texas Instruments")
        (field (name "SYMBOLCREATOR") "x0120606")
      )
      (libsource (lib "TI-INDIA-ALTIUM") (part "TPS7A3001DGNR"))
    )
    (comp (ref "U22")
      (value "TLV70450DBV")
      (footprint "DBV0005A_N")
      (description "Regulator, LDO, 5V, 0.15A, SOT23-5")
      (fields
        (field (name "MANUFACTURER") "Texas Instruments")
        (field (name "SYMBOLCREATOR") "x0120606")
        (field (name "PUBLISHER") "Texas Instruments")
      )
      (libsource (lib "TI-INDIA-ALTIUM") (part "TLV70450DBV"))
    )
    (comp (ref "U23")
      (value "TPS7A3001DGNR")
      (footprint "MSOP8(DGN)")
      (description "-36V, -200mA, Ultralow-Noise, Negative Linear Regulator")
      (fields
        (field (name "MANUFACTURER") "Texas Instruments")
        (field (name "PUBLISHER") "Texas Instruments")
        (field (name "SYMBOLCREATOR") "x0120606")
      )
      (libsource (lib "TI-INDIA-ALTIUM") (part "TPS7A3001DGNR"))
    )
    (comp (ref "U24")
      (value "TLV70450DBV")
      (footprint "DBV0005A_N")
      (description "Regulator, LDO, 5V, 0.15A, SOT23-5")
      (fields
        (field (name "MANUFACTURER") "Texas Instruments")
        (field (name "SYMBOLCREATOR") "x0120606")
        (field (name "PUBLISHER") "Texas Instruments")
      )
      (libsource (lib "TI-INDIA-ALTIUM") (part "TLV70450DBV"))
    )
  )
  (nets
    (net (code "1") (name "+5.0V_USH") (class "Default")
      (node (ref "C151") (pin "2") (pinfunction "2_2") (pintype "passive"))
      (node (ref "C152") (pin "1") (pinfunction "1_1") (pintype "passive"))
      (node (ref "D46") (pin "1") (pinfunction "K_1") (pintype "passive"))
      (node (ref "FB22") (pin "2") (pinfunction "2_2") (pintype "passive"))
      (node (ref "R105") (pin "2") (pinfunction "2_2") (pintype "passive"))
    )
    (net (code "2") (name "+5.0V_VSH") (class "Default")
      (node (ref "C135") (pin "2") (pinfunction "2_2") (pintype "passive"))
      (node (ref "C136") (pin "1") (pinfunction "1_1") (pintype "passive"))
      (node (ref "D40") (pin "1") (pinfunction "K_1") (pintype "passive"))
      (node (ref "FB20") (pin "2") (pinfunction "2_2") (pintype "passive"))
      (node (ref "R7") (pin "2") (pinfunction "2_2") (pintype "passive"))
    )
    (net (code "3") (name "+5V_CNTL") (class "Default")
      (node (ref "C13") (pin "2") (pinfunction "2_2") (pintype "passive"))
      (node (ref "C14") (pin "2") (pinfunction "2_2") (pintype "passive"))
      (node (ref "C16") (pin "1") (pinfunction "+_1") (pintype "passive"))
      (node (ref "C5") (pin "2") (pinfunction "2_2") (pintype "passive"))
      (node (ref "C6") (pin "2") (pinfunction "2_2") (pintype "passive"))
      (node (ref "T1") (pin "2") (pinfunction "2_2") (pintype "passive"))
      (node (ref "T2") (pin "2") (pinfunction "2_2") (pintype "passive"))
      (node (ref "U2") (pin "2") (pinfunction "VCC_2") (pintype "power_in"))
      (node (ref "U4") (pin "2") (pinfunction "VCC_2") (pintype "power_in"))
    )
    (net (code "4") (name "+6V_USH") (class "Default")
      (node (ref "C144") (pin "1") (pinfunction "1_1") (pintype "passive"))
      (node (ref "C145") (pin "1") (pinfunction "1_1") (pintype "passive"))
      (node (ref "C149") (pin "2") (pinfunction "2_2") (pintype "passive"))
      (node (ref "C150") (pin "1") (pinfunction "1_1") (pintype "passive"))
      (node (ref "D45") (pin "1") (pinfunction "K_1") (pintype "passive"))
      (node (ref "U24") (pin "2") (pinfunction "IN_2") (pintype "input"))
    )
    (net (code "5") (name "+6V_VSH") (class "Default")
      (node (ref "C128") (pin "1") (pinfunction "1_1") (pintype "passive"))
      (node (ref "C129") (pin "1") (pinfunction "1_1") (pintype "passive"))
      (node (ref "C133") (pin "2") (pinfunction "2_2") (pintype "passive"))
      (node (ref "C134") (pin "1") (pinfunction "1_1") (pintype "passive"))
      (node (ref "D39") (pin "1") (pinfunction "K_1") (pintype "passive"))
      (node (ref "U22") (pin "2") (pinfunction "IN_2") (pintype "input"))
    )
    (net (code "6") (name "-5.0V_USH") (class "Default")
      (node (ref "C138") (pin "1") (pinfunction "1_1") (pintype "passive"))
      (node (ref "C142") (pin "2") (pinfunction "2_2") (pintype "passive"))
      (node (ref "D44") (pin "2") (pinfunction "A_2") (pintype "passive"))
      (node (ref "FB21") (pin "2") (pinfunction "2_2") (pintype "passive"))
      (node (ref "R6") (pin "2") (pinfunction "2_2") (pintype "passive"))
      (node (ref "TP3") (pin "1") (pinfunction "1_1") (pintype "passive"))
    )
    (net (code "7") (name "-5.0V_VSH") (class "Default")
      (node (ref "C122") (pin "1") (pinfunction "1_1") (pintype "passive"))
      (node (ref "C126") (pin "2") (pinfunction "2_2") (pintype "passive"))
      (node (ref "D38") (pin "2") (pinfunction "A_2") (pintype "passive"))
      (node (ref "FB19") (pin "2") (pinfunction "2_2") (pintype "passive"))
      (node (ref "R19") (pin "2") (pinfunction "2_2") (pintype "passive"))
      (node (ref "TP6") (pin "1") (pinfunction "1_1") (pintype "passive"))
    )
    (net (code "8") (name "-6V_USH") (class "Default")
      (node (ref "C139") (pin "2") (pinfunction "2_2") (pintype "passive"))
      (node (ref "C141") (pin "2") (pinfunction "2_2") (pintype "passive"))
      (node (ref "C146") (pin "1") (pinfunction "1_1") (pintype "passive"))
      (node (ref "C148") (pin "2") (pinfunction "2_2") (pintype "passive"))
      (node (ref "D43") (pin "2") (pinfunction "A_2") (pintype "passive"))
      (node (ref "U23") (pin "5") (pinfunction "EN_5") (pintype "input"))
      (node (ref "U23") (pin "8") (pinfunction "VIN_8") (pintype "power_in"))
    )
    (net (code "9") (name "-6V_VSH") (class "Default")
      (node (ref "C123") (pin "2") (pinfunction "2_2") (pintype "passive"))
      (node (ref "C125") (pin "2") (pinfunction "2_2") (pintype "passive"))
      (node (ref "C130") (pin "1") (pinfunction "1_1") (pintype "passive"))
      (node (ref "C132") (pin "2") (pinfunction "2_2") (pintype "passive"))
      (node (ref "D37") (pin "2") (pinfunction "A_2") (pintype "passive"))
      (node (ref "U21") (pin "5") (pinfunction "EN_5") (pintype "input"))
      (node (ref "U21") (pin "8") (pinfunction "VIN_8") (pintype "power_in"))
    )
    (net (code "10") (name "DGND") (class "Default")
      (node (ref "C13") (pin "1") (pinfunction "1_1") (pintype "passive"))
      (node (ref "C14") (pin "1") (pinfunction "1_1") (pintype "passive"))
      (node (ref "C15") (pin "1") (pinfunction "1_1") (pintype "passive"))
      (node (ref "C16") (pin "2") (pinfunction "-_2") (pintype "passive"))
      (node (ref "C5") (pin "1") (pinfunction "1_1") (pintype "passive"))
      (node (ref "C6") (pin "1") (pinfunction "1_1") (pintype "passive"))
      (node (ref "C7") (pin "1") (pinfunction "1_1") (pintype "passive"))
      (node (ref "U2") (pin "4") (pinfunction "GND_4") (pintype "power_in"))
      (node (ref "U2") (pin "5") (pinfunction "GND_5") (pintype "power_in"))
      (node (ref "U4") (pin "4") (pinfunction "GND_4") (pintype "power_in"))
      (node (ref "U4") (pin "5") (pinfunction "GND_5") (pintype "power_in"))
    )
    (net (code "11") (name "GND_USH") (class "Default")
      (node (ref "C138") (pin "2") (pinfunction "2_2") (pintype "passive"))
      (node (ref "C139") (pin "1") (pinfunction "1_1") (pintype "passive"))
      (node (ref "C140") (pin "1") (pinfunction "1_1") (pintype "passive"))
      (node (ref "C141") (pin "1") (pinfunction "1_1") (pintype "passive"))
      (node (ref "C142") (pin "1") (pinfunction "1_1") (pintype "passive"))
      (node (ref "C144") (pin "2") (pinfunction "2_2") (pintype "passive"))
      (node (ref "C145") (pin "2") (pinfunction "2_2") (pintype "passive"))
      (node (ref "C146") (pin "2") (pinfunction "2_2") (pintype "passive"))
      (node (ref "C147") (pin "1") (pinfunction "1_1") (pintype "passive"))
      (node (ref "C148") (pin "1") (pinfunction "1_1") (pintype "passive"))
      (node (ref "C149") (pin "1") (pinfunction "1_1") (pintype "passive"))
      (node (ref "C150") (pin "2") (pinfunction "2_2") (pintype "passive"))
      (node (ref "C151") (pin "1") (pinfunction "1_1") (pintype "passive"))
      (node (ref "C152") (pin "2") (pinfunction "2_2") (pintype "passive"))
      (node (ref "C153") (pin "1") (pinfunction "1_1") (pintype "passive"))
      (node (ref "C7") (pin "2") (pinfunction "2_2") (pintype "passive"))
      (node (ref "D1") (pin "1") (pinfunction "C_1") (pintype "passive"))
      (node (ref "D2") (pin "2") (pinfunction "A_2") (pintype "passive"))
      (node (ref "D44") (pin "1") (pinfunction "K_1") (pintype "passive"))
      (node (ref "D46") (pin "2") (pinfunction "A_2") (pintype "passive"))
      (node (ref "R103") (pin "1") (pinfunction "1_1") (pintype "passive"))
      (node (ref "T1") (pin "4") (pinfunction "4_4") (pintype "passive"))
      (node (ref "U23") (pin "3") (pinfunction "NC_3") (pintype "passive"))
      (node (ref "U23") (pin "4") (pinfunction "GND_4") (pintype "power_in"))
      (node (ref "U23") (pin "9") (pinfunction "TPAD_9") (pintype "passive"))
      (node (ref "U24") (pin "1") (pinfunction "GND_1") (pintype "power_in"))
    )
    (net (code "12") (name "GND_VSH") (class "Default")
      (node (ref "C122") (pin "2") (pinfunction "2_2") (pintype "passive"))
      (node (ref "C123") (pin "1") (pinfunction "1_1") (pintype "passive"))
      (node (ref "C124") (pin "1") (pinfunction "1_1") (pintype "passive"))
      (node (ref "C125") (pin "1") (pinfunction "1_1") (pintype "passive"))
      (node (ref "C126") (pin "1") (pinfunction "1_1") (pintype "passive"))
      (node (ref "C128") (pin "2") (pinfunction "2_2") (pintype "passive"))
      (node (ref "C129") (pin "2") (pinfunction "2_2") (pintype "passive"))
      (node (ref "C130") (pin "2") (pinfunction "2_2") (pintype "passive"))
      (node (ref "C131") (pin "1") (pinfunction "1_1") (pintype "passive"))
      (node (ref "C132") (pin "1") (pinfunction "1_1") (pintype "passive"))
      (node (ref "C133") (pin "1") (pinfunction "1_1") (pintype "passive"))
      (node (ref "C134") (pin "2") (pinfunction "2_2") (pintype "passive"))
      (node (ref "C135") (pin "1") (pinfunction "1_1") (pintype "passive"))
      (node (ref "C136") (pin "2") (pinfunction "2_2") (pintype "passive"))
      (node (ref "C137") (pin "1") (pinfunction "1_1") (pintype "passive"))
      (node (ref "C15") (pin "2") (pinfunction "2_2") (pintype "passive"))
      (node (ref "D3") (pin "1") (pinfunction "C_1") (pintype "passive"))
      (node (ref "D38") (pin "1") (pinfunction "K_1") (pintype "passive"))
      (node (ref "D4") (pin "2") (pinfunction "A_2") (pintype "passive"))
      (node (ref "D40") (pin "2") (pinfunction "A_2") (pintype "passive"))
      (node (ref "R101") (pin "1") (pinfunction "1_1") (pintype "passive"))
      (node (ref "T2") (pin "4") (pinfunction "4_4") (pintype "passive"))
      (node (ref "U21") (pin "3") (pinfunction "NC_3") (pintype "passive"))
      (node (ref "U21") (pin "4") (pinfunction "GND_4") (pintype "power_in"))
      (node (ref "U21") (pin "9") (pinfunction "TPAD_9") (pintype "passive"))
      (node (ref "U22") (pin "1") (pinfunction "GND_1") (pintype "power_in"))
    )
    (net (code "13") (name "Net-(D1-A)") (class "Default")
      (node (ref "D1") (pin "2") (pinfunction "A_2") (pintype "passive"))
      (node (ref "R105") (pin "1") (pinfunction "1_1") (pintype "passive"))
    )
    (net (code "14") (name "Net-(D2-C)") (class "Default")
      (node (ref "D2") (pin "1") (pinfunction "C_1") (pintype "passive"))
      (node (ref "R6") (pin "1") (pinfunction "1_1") (pintype "passive"))
    )
    (net (code "15") (name "Net-(D3-A)") (class "Default")
      (node (ref "D3") (pin "2") (pinfunction "A_2") (pintype "passive"))
      (node (ref "R7") (pin "1") (pinfunction "1_1") (pintype "passive"))
    )
    (net (code "16") (name "Net-(D4-C)") (class "Default")
      (node (ref "D4") (pin "1") (pinfunction "C_1") (pintype "passive"))
      (node (ref "R19") (pin "1") (pinfunction "1_1") (pintype "passive"))
    )
    (net (code "17") (name "Net-(D37-K)") (class "Default")
      (node (ref "D37") (pin "1") (pinfunction "K_1") (pintype "passive"))
      (node (ref "D39") (pin "2") (pinfunction "A_2") (pintype "passive"))
      (node (ref "T2") (pin "6") (pinfunction "6_6") (pintype "passive"))
    )
    (net (code "18") (name "Net-(D43-K)") (class "Default")
      (node (ref "D43") (pin "1") (pinfunction "K_1") (pintype "passive"))
      (node (ref "D45") (pin "2") (pinfunction "A_2") (pintype "passive"))
      (node (ref "T1") (pin "6") (pinfunction "6_6") (pintype "passive"))
    )
    (net (code "19") (name "Net-(U2-D1)") (class "Default")
      (node (ref "T1") (pin "3") (pinfunction "3_3") (pintype "passive"))
      (node (ref "U2") (pin "1") (pinfunction "D1_1") (pintype "output"))
    )
    (net (code "20") (name "Net-(U2-D2)") (class "Default")
      (node (ref "T1") (pin "1") (pinfunction "1_1") (pintype "passive"))
      (node (ref "U2") (pin "3") (pinfunction "D2_3") (pintype "output"))
    )
    (net (code "21") (name "Net-(U4-D1)") (class "Default")
      (node (ref "T2") (pin "3") (pinfunction "3_3") (pintype "passive"))
      (node (ref "U4") (pin "1") (pinfunction "D1_1") (pintype "output"))
    )
    (net (code "22") (name "Net-(U4-D2)") (class "Default")
      (node (ref "T2") (pin "1") (pinfunction "1_1") (pintype "passive"))
      (node (ref "U4") (pin "3") (pinfunction "D2_3") (pintype "output"))
    )
    (net (code "23") (name "Net-(U21-FB)") (class "Default")
      (node (ref "C127") (pin "1") (pinfunction "1_1") (pintype "passive"))
      (node (ref "R101") (pin "2") (pinfunction "2_2") (pintype "passive"))
      (node (ref "R102") (pin "1") (pinfunction "1_1") (pintype "passive"))
      (node (ref "U21") (pin "2") (pinfunction "FB_2") (pintype "input"))
    )
    (net (code "24") (name "Net-(U21-NR{slash}SS)") (class "Default")
      (node (ref "C124") (pin "2") (pinfunction "2_2") (pintype "passive"))
      (node (ref "U21") (pin "6") (pinfunction "NR/SS_6") (pintype "input"))
    )
    (net (code "25") (name "Net-(U21-OUT)") (class "Default")
      (node (ref "C127") (pin "2") (pinfunction "2_2") (pintype "passive"))
      (node (ref "C131") (pin "2") (pinfunction "2_2") (pintype "passive"))
      (node (ref "FB19") (pin "1") (pinfunction "1_1") (pintype "passive"))
      (node (ref "R102") (pin "2") (pinfunction "2_2") (pintype "passive"))
      (node (ref "U21") (pin "1") (pinfunction "OUT_1") (pintype "power_in"))
    )
    (net (code "26") (name "Net-(U22-OUT)") (class "Default")
      (node (ref "C137") (pin "2") (pinfunction "2_2") (pintype "passive"))
      (node (ref "FB20") (pin "1") (pinfunction "1_1") (pintype "passive"))
      (node (ref "U22") (pin "3") (pinfunction "OUT_3") (pintype "output"))
    )
    (net (code "27") (name "Net-(U23-FB)") (class "Default")
      (node (ref "C143") (pin "1") (pinfunction "1_1") (pintype "passive"))
      (node (ref "R103") (pin "2") (pinfunction "2_2") (pintype "passive"))
      (node (ref "R104") (pin "1") (pinfunction "1_1") (pintype "passive"))
      (node (ref "U23") (pin "2") (pinfunction "FB_2") (pintype "input"))
    )
    (net (code "28") (name "Net-(U23-NR{slash}SS)") (class "Default")
      (node (ref "C140") (pin "2") (pinfunction "2_2") (pintype "passive"))
      (node (ref "U23") (pin "6") (pinfunction "NR/SS_6") (pintype "input"))
    )
    (net (code "29") (name "Net-(U23-OUT)") (class "Default")
      (node (ref "C143") (pin "2") (pinfunction "2_2") (pintype "passive"))
      (node (ref "C147") (pin "2") (pinfunction "2_2") (pintype "passive"))
      (node (ref "FB21") (pin "1") (pinfunction "1_1") (pintype "passive"))
      (node (ref "R104") (pin "2") (pinfunction "2_2") (pintype "passive"))
      (node (ref "U23") (pin "1") (pinfunction "OUT_1") (pintype "power_in"))
    )
    (net (code "30") (name "Net-(U24-OUT)") (class "Default")
      (node (ref "C153") (pin "2") (pinfunction "2_2") (pintype "passive"))
      (node (ref "FB22") (pin "1") (pinfunction "1_1") (pintype "passive"))
      (node (ref "U24") (pin "3") (pinfunction "OUT_3") (pintype "output"))
    )
    (net (code "31") (name "unconnected-(T1-Pad5)") (class "Default")
      (node (ref "T1") (pin "5") (pinfunction "5_5") (pintype "passive"))
    )
    (net (code "32") (name "unconnected-(T2-Pad5)") (class "Default")
      (node (ref "T2") (pin "5") (pinfunction "5_5") (pintype "passive"))
    )
    (net (code "33") (name "unconnected-(U21-DNC-Pad7)") (class "Default")
      (node (ref "U21") (pin "7") (pinfunction "DNC_7") (pintype "passive"))
    )
    (net (code "34") (name "unconnected-(U22-NC-Pad4)") (class "Default")
      (node (ref "U22") (pin "4") (pinfunction "NC_4") (pintype "power_in"))
    )
    (net (code "35") (name "unconnected-(U22-NC-Pad5)") (class "Default")
      (node (ref "U22") (pin "5") (pinfunction "NC_5") (pintype "power_in"))
    )
    (net (code "36") (name "unconnected-(U23-DNC-Pad7)") (class "Default")
      (node (ref "U23") (pin "7") (pinfunction "DNC_7") (pintype "passive"))
    )
    (net (code "37") (name "unconnected-(U24-NC-Pad4)") (class "Default")
      (node (ref "U24") (pin "4") (pinfunction "NC_4") (pintype "power_in"))
    )
    (net (code "38") (name "unconnected-(U24-NC-Pad5)") (class "Default")
      (node (ref "U24") (pin "5") (pinfunction "NC_5") (pintype "power_in"))
    )
  )
)
